# USBSocket_Type2_v1_0.net
KiCad netlist of a schematic drawn in EAGLE
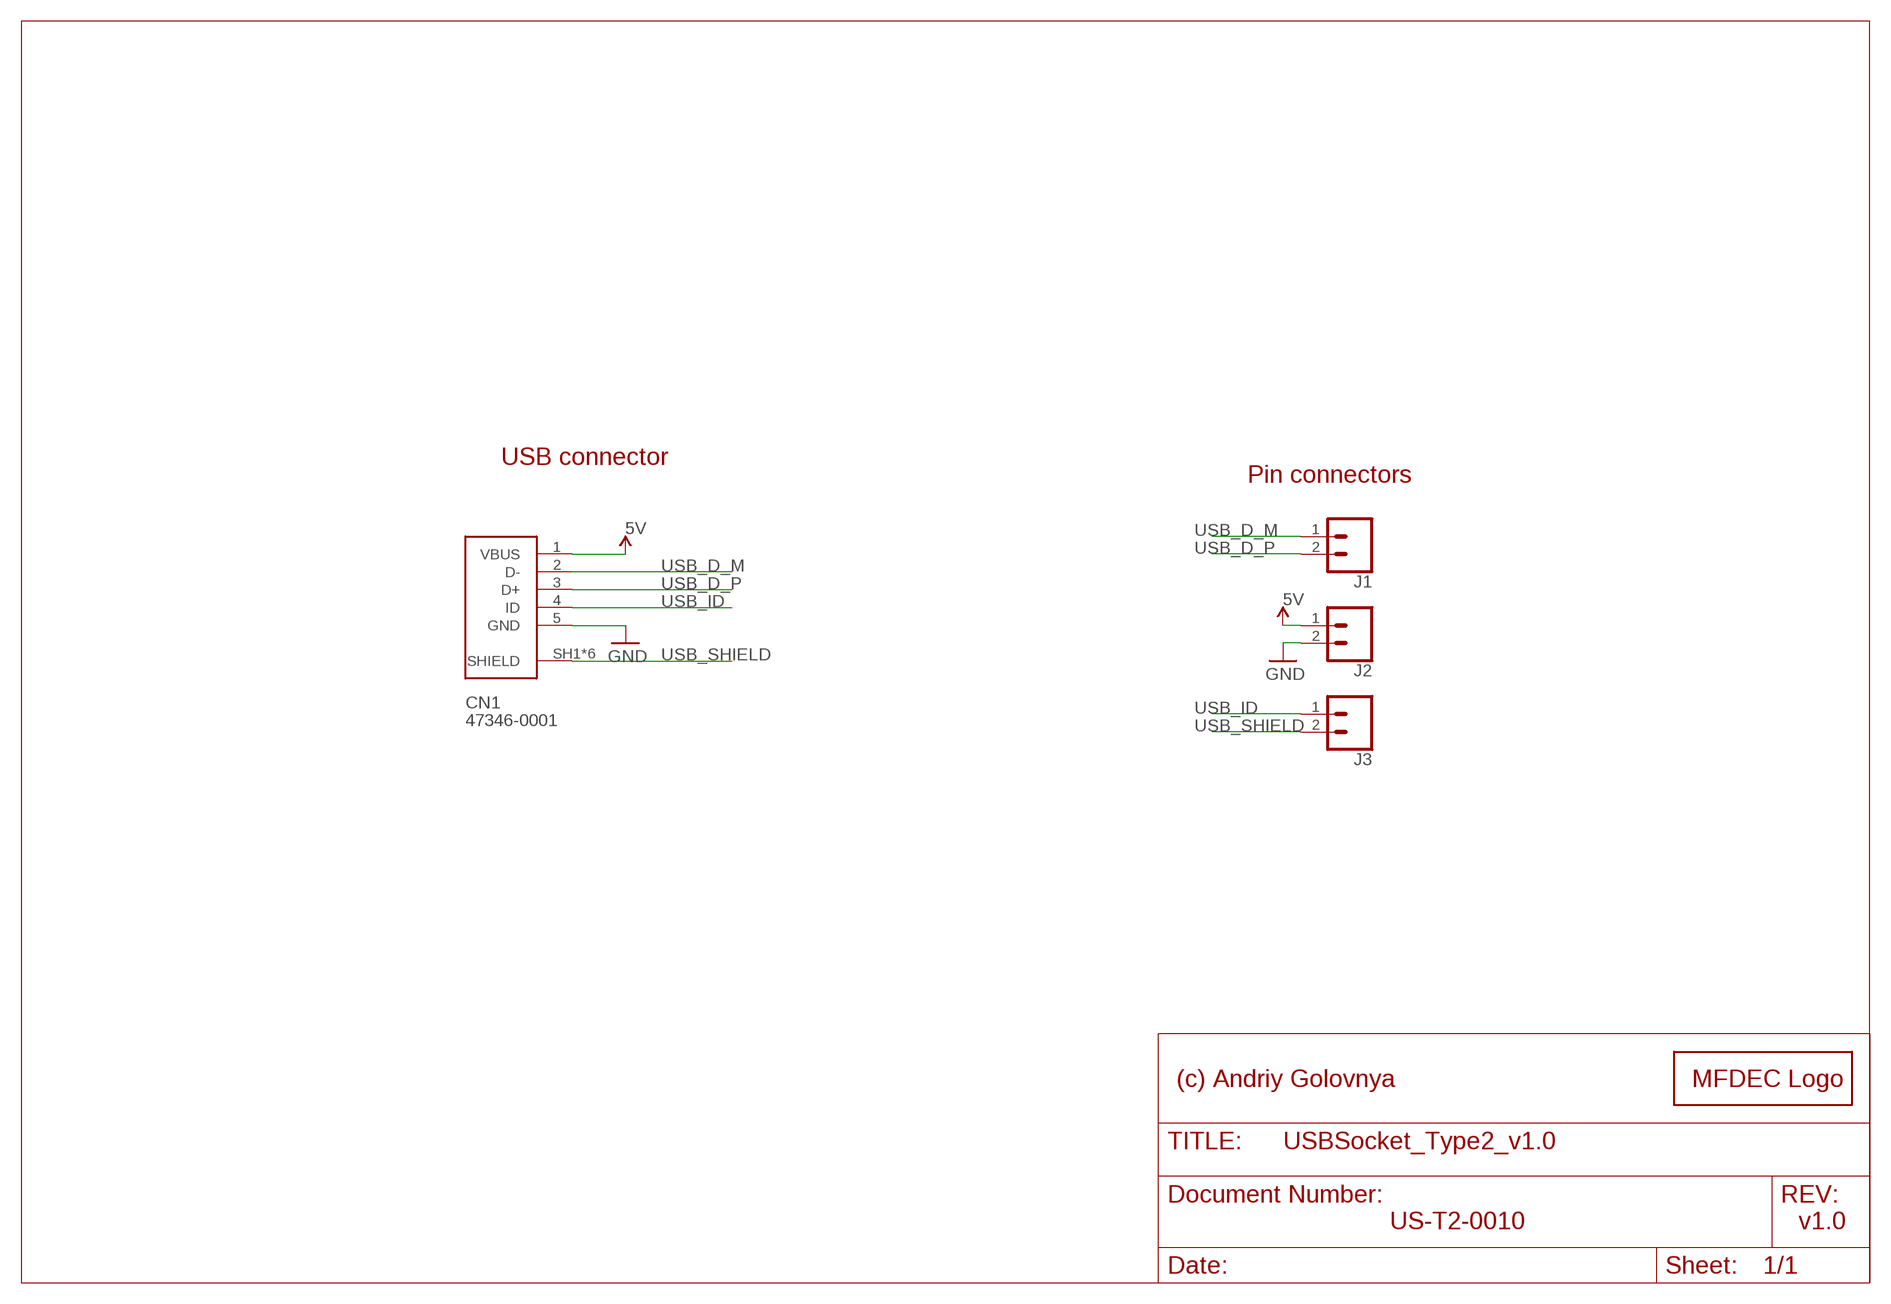
[diagram p0: schematic, sheet 1]

(export (version "E")
  (design (tool "Eeschema 10.0.6"))
  (components
    (comp (ref "CN1")
      (value "47346-0001")
      (footprint "eagle-import:MOLEX_47346-0001")
      (fields (field (name "MANUFACTURER") "Molex"))
      (libsource (lib "eagle-import") (part "47346-0001"))
    )
    (comp (ref "J1")
      (value "CONN_02")
      (footprint "eagle-import:1X02")
      (libsource (lib "eagle-import") (part "CONN_02"))
    )
    (comp (ref "J2")
      (value "CONN_02")
      (footprint "eagle-import:1X02")
      (libsource (lib "eagle-import") (part "CONN_02"))
    )
    (comp (ref "J3")
      (value "CONN_02")
      (footprint "eagle-import:1X02")
      (libsource (lib "eagle-import") (part "CONN_02"))
    )
    (comp (ref "LOGO1")
      (value "MFDECLOGO_L_10MM")
      (footprint "eagle-import:MFDEC_L_10MM")
      (libsource (lib "eagle-import") (part "MFDECLOGO_L_10MM"))
    )
  )
  (nets
    (net (code "1") (name "/USB_D_M") (class "Default")
      (node (ref "CN1") (pin "2") (pinfunction "D-_2") (pintype "bidirectional"))
      (node (ref "J1") (pin "1") (pinfunction "1_1") (pintype "passive"))
    )
    (net (code "2") (name "/USB_D_P") (class "Default")
      (node (ref "CN1") (pin "3") (pinfunction "D+_3") (pintype "bidirectional"))
      (node (ref "J1") (pin "2") (pinfunction "2_2") (pintype "passive"))
    )
    (net (code "3") (name "/USB_ID") (class "Default")
      (node (ref "CN1") (pin "4") (pinfunction "ID_4") (pintype "passive"))
      (node (ref "J3") (pin "1") (pinfunction "1_1") (pintype "passive"))
    )
    (net (code "4") (name "/USB_SHIELD") (class "Default")
      (node (ref "CN1") (pin "SH1") (pinfunction "SHIELD_SH1") (pintype "passive"))
      (node (ref "CN1") (pin "SH2") (pinfunction "SHIELD_SH2") (pintype "passive"))
      (node (ref "CN1") (pin "SH3") (pinfunction "SHIELD_SH3") (pintype "passive"))
      (node (ref "CN1") (pin "SH4") (pinfunction "SHIELD_SH4") (pintype "passive"))
      (node (ref "CN1") (pin "SH5") (pinfunction "SHIELD_SH5") (pintype "passive"))
      (node (ref "CN1") (pin "SH6") (pinfunction "SHIELD_SH6") (pintype "passive"))
      (node (ref "J3") (pin "2") (pinfunction "2_2") (pintype "passive"))
    )
    (net (code "5") (name "5V") (class "Default")
      (node (ref "CN1") (pin "1") (pinfunction "VBUS_1") (pintype "power_in"))
      (node (ref "J2") (pin "1") (pinfunction "1_1") (pintype "passive"))
    )
    (net (code "6") (name "GND") (class "Default")
      (node (ref "CN1") (pin "5") (pinfunction "GND_5") (pintype "power_in"))
      (node (ref "J2") (pin "2") (pinfunction "2_2") (pintype "passive"))
    )
  )
)
